# relay_m66.net
KiCad netlist of a schematic drawn in Altium Designer
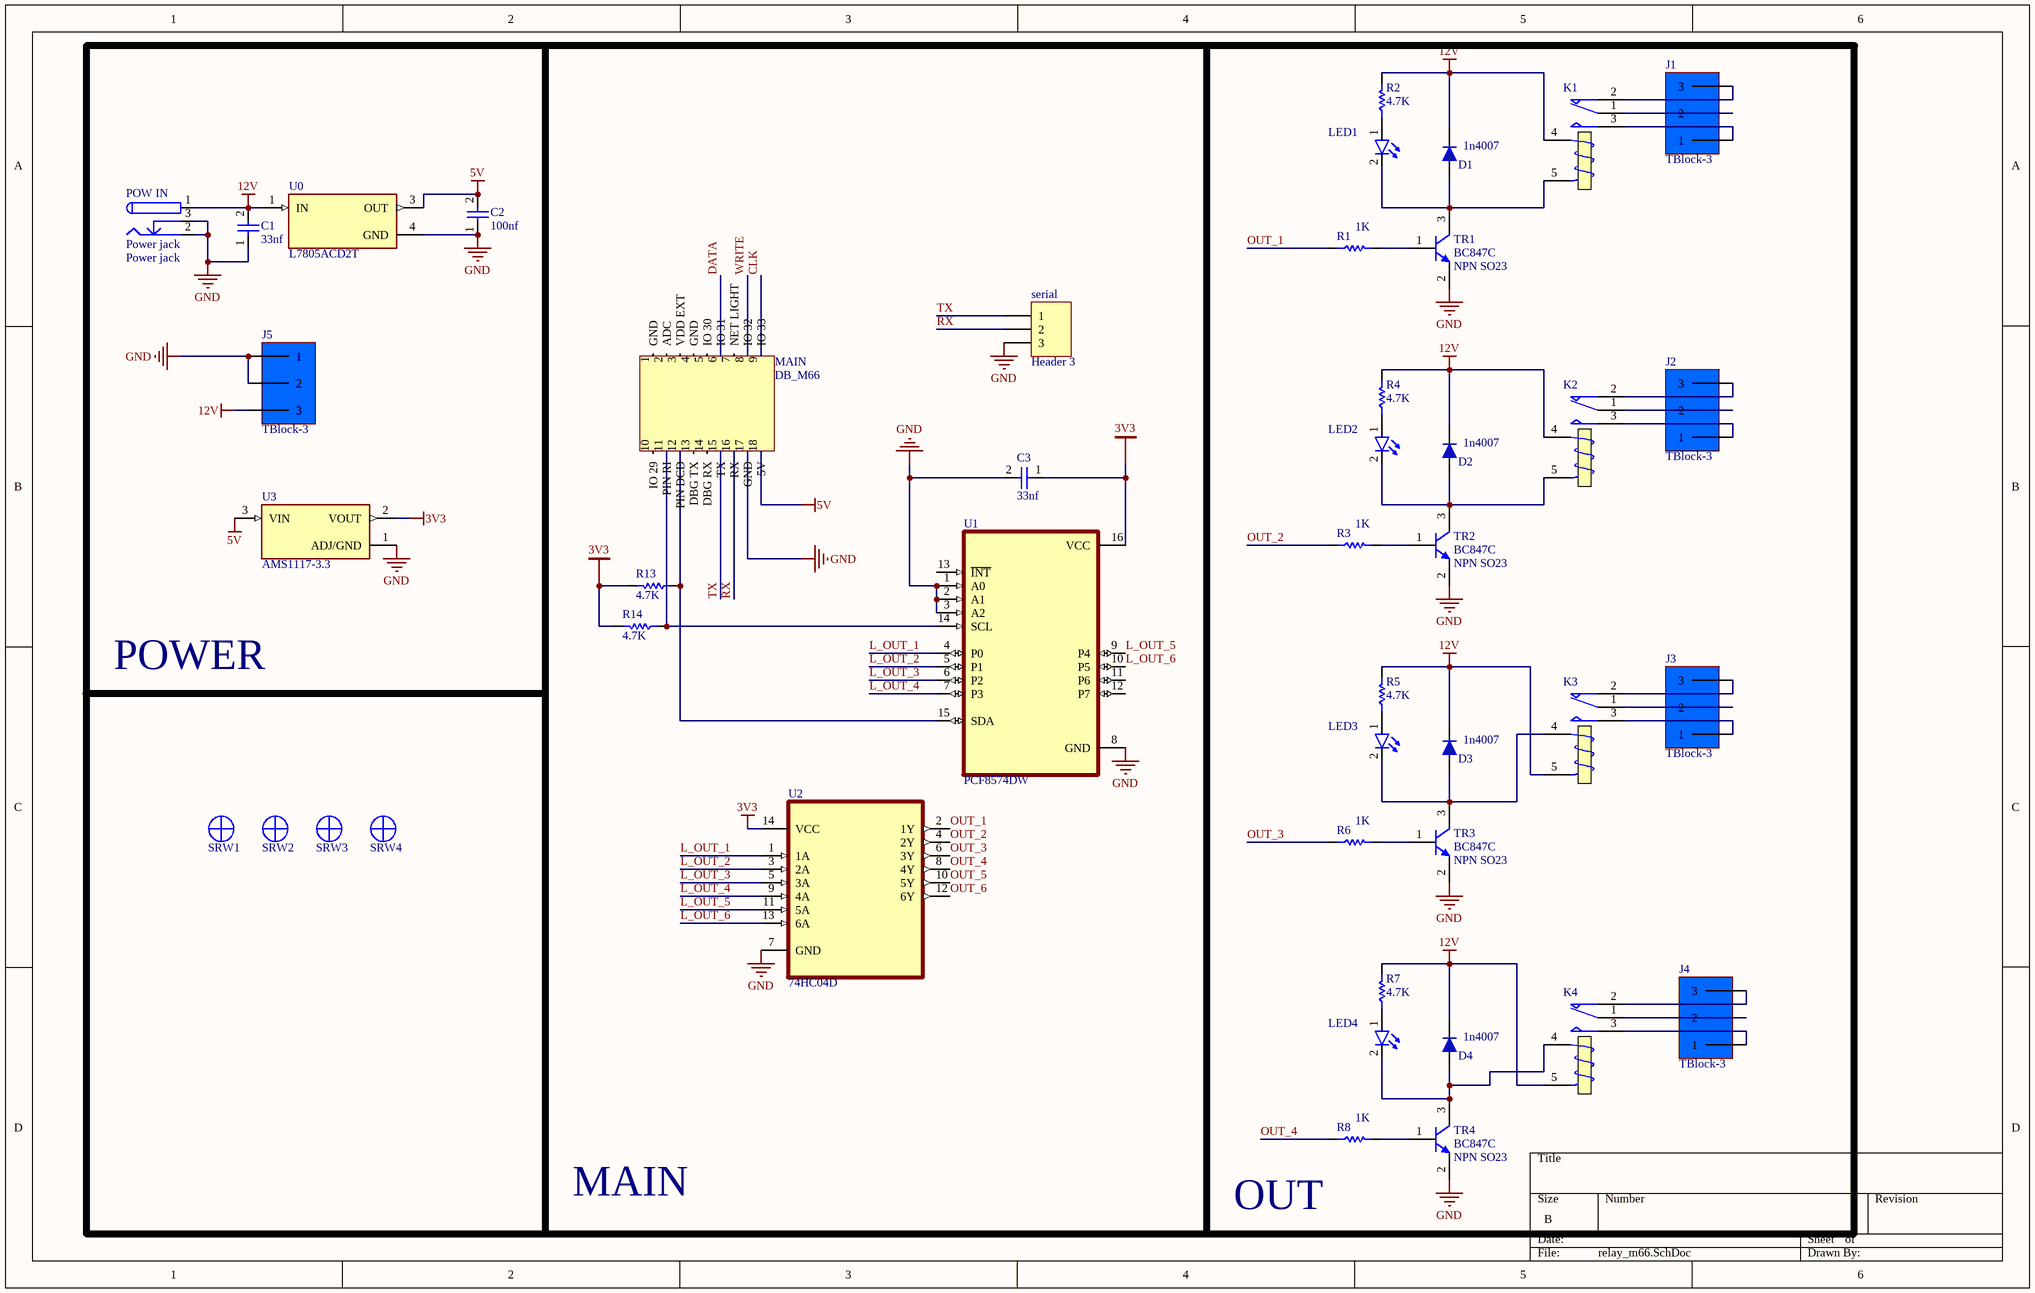
[diagram p0: relay_m66.SchDoc]

(export (version "E")
  (design (tool "Eeschema 10.0.6"))
  (components
    (comp (ref "C1") (value "33nf") (footprint "SMD 0805") (libsource (lib "3D LIB") (part "CAP NON")))
    (comp (ref "C2") (value "100nf") (footprint "SMD 0805") (libsource (lib "3D LIB") (part "CAP NON")))
    (comp (ref "C3") (value "33nf") (footprint "SMD 0805") (libsource (lib "3D LIB") (part "CAP NON")))
    (comp (ref "D1")
      (value "1n4007")
      (footprint "DIOM4629X24N")
      (description "Standard Rectifiers")
      (fields (field (name "MANUFACTURER") "DC COMPONENTS") (field (name "DESIGNER") "Abbas Basereh"))
      (libsource (lib "Altium") (part "1n4007 SMD M7"))
    )
    (comp (ref "D2")
      (value "1n4007")
      (footprint "DIOM4629X24N")
      (description "Standard Rectifiers")
      (fields (field (name "MANUFACTURER") "DC COMPONENTS") (field (name "DESIGNER") "Abbas Basereh"))
      (libsource (lib "Altium") (part "1n4007 SMD M7"))
    )
    (comp (ref "D3")
      (value "1n4007")
      (footprint "DIOM4629X24N")
      (description "Standard Rectifiers")
      (fields (field (name "MANUFACTURER") "DC COMPONENTS") (field (name "DESIGNER") "Abbas Basereh"))
      (libsource (lib "Altium") (part "1n4007 SMD M7"))
    )
    (comp (ref "D4")
      (value "1n4007")
      (footprint "DIOM4629X24N")
      (description "Standard Rectifiers")
      (fields (field (name "MANUFACTURER") "DC COMPONENTS") (field (name "DESIGNER") "Abbas Basereh"))
      (libsource (lib "Altium") (part "1n4007 SMD M7"))
    )
    (comp (ref "J1")
      (value "TBlock-3")
      (footprint "KF300-3 PIN")
      (libsource (lib "AltiumLib1") (part "TBlock-3"))
    )
    (comp (ref "J2")
      (value "TBlock-3")
      (footprint "KF300-3 PIN")
      (libsource (lib "AltiumLib1") (part "TBlock-3"))
    )
    (comp (ref "J3")
      (value "TBlock-3")
      (footprint "KF300-3 PIN")
      (libsource (lib "AltiumLib1") (part "TBlock-3"))
    )
    (comp (ref "J4")
      (value "TBlock-3")
      (footprint "KF300-3 PIN")
      (libsource (lib "AltiumLib1") (part "TBlock-3"))
    )
    (comp (ref "J5") (value "TBlock-3") (footprint "KF300-3 PIN") (libsource (lib "") (part "TBlock-3_1")))
    (comp (ref "K1")
      (value "~")
      (footprint "Relay 18.85x15.35x15.70")
      (description "Single-Pole Dual-Throw Relay")
      (fields (field (name "DESIGNER") "Abbas Basereh"))
      (libsource (lib "2017Basereh -ver1") (part "Relay_SPDT"))
    )
    (comp (ref "K2")
      (value "~")
      (footprint "Relay 18.85x15.35x15.70")
      (description "Single-Pole Dual-Throw Relay")
      (fields (field (name "DESIGNER") "Abbas Basereh"))
      (libsource (lib "2017Basereh -ver1") (part "Relay_SPDT"))
    )
    (comp (ref "K3")
      (value "~")
      (footprint "Relay 18.85x15.35x15.70")
      (description "Single-Pole Dual-Throw Relay")
      (fields (field (name "DESIGNER") "Abbas Basereh"))
      (libsource (lib "2017Basereh -ver1") (part "Relay_SPDT"))
    )
    (comp (ref "K4")
      (value "~")
      (footprint "Relay 18.85x15.35x15.70")
      (description "Single-Pole Dual-Throw Relay")
      (fields (field (name "DESIGNER") "Abbas Basereh"))
      (libsource (lib "2017Basereh -ver1") (part "Relay_SPDT"))
    )
    (comp (ref "LED1") (value "LED 2PIN") (footprint "LED 0805") (libsource (lib "3D LIB") (part "LED 2PIN")))
    (comp (ref "LED2") (value "LED 2PIN") (footprint "LED 0805") (libsource (lib "3D LIB") (part "LED 2PIN")))
    (comp (ref "LED3") (value "LED 2PIN") (footprint "LED 0805") (libsource (lib "3D LIB") (part "LED 2PIN")))
    (comp (ref "LED4") (value "LED 2PIN") (footprint "LED 0805") (libsource (lib "3D LIB") (part "LED 2PIN")))
    (comp (ref "MAIN") (value "DB_M66") (footprint "DB_M66") (libsource (lib "mahdi_h") (part "DB_M66")))
    (comp (ref "POW IN")
      (value "Power jack")
      (footprint "Power Jack")
      (fields (field (name "ALTIUM_UNNAMED_1") "Power jack"))
      (libsource (lib "3D LIB") (part "Power jack"))
    )
    (comp (ref "R1") (value "1K") (footprint "0805_1/8W") (libsource (lib "3D LIB") (part "RESISTOR")))
    (comp (ref "R2") (value "4.7K") (footprint "0805_1/8W") (libsource (lib "3D LIB") (part "RESISTOR")))
    (comp (ref "R3") (value "1K") (footprint "0805_1/8W") (libsource (lib "3D LIB") (part "RESISTOR")))
    (comp (ref "R4") (value "4.7K") (footprint "0805_1/8W") (libsource (lib "3D LIB") (part "RESISTOR")))
    (comp (ref "R5") (value "4.7K") (footprint "0805_1/8W") (libsource (lib "3D LIB") (part "RESISTOR")))
    (comp (ref "R6") (value "1K") (footprint "0805_1/8W") (libsource (lib "3D LIB") (part "RESISTOR")))
    (comp (ref "R7") (value "4.7K") (footprint "0805_1/8W") (libsource (lib "3D LIB") (part "RESISTOR")))
    (comp (ref "R8") (value "1K") (footprint "0805_1/8W") (libsource (lib "3D LIB") (part "RESISTOR")))
    (comp (ref "R13") (value "4.7K") (footprint "0805_1/8W") (libsource (lib "3D LIB") (part "RESISTOR")))
    (comp (ref "R14") (value "4.7K") (footprint "0805_1/8W") (libsource (lib "3D LIB") (part "RESISTOR")))
    (comp (ref "serial")
      (value "Header 3")
      (footprint "HDR1X3")
      (description "Header, 3-Pin")
      (fields (field (name "PUBLISHER") "Altium Limited"))
      (libsource (lib "Miscellaneous Connectors") (part "Header 3"))
    )
    (comp (ref "SRW1")
      (value "Screw")
      (footprint "Board Screw")
      (description "Board Screw With Spacer")
      (libsource (lib "Altium") (part "Board Screw 3MM"))
    )
    (comp (ref "SRW2")
      (value "Screw")
      (footprint "Board Screw")
      (description "Board Screw With Spacer")
      (libsource (lib "Altium") (part "Board Screw 3MM"))
    )
    (comp (ref "SRW3")
      (value "Screw")
      (footprint "Board Screw")
      (description "Board Screw With Spacer")
      (libsource (lib "Altium") (part "Board Screw 3MM"))
    )
    (comp (ref "SRW4")
      (value "Screw")
      (footprint "Board Screw")
      (description "Board Screw With Spacer")
      (libsource (lib "Altium") (part "Board Screw 3MM"))
    )
    (comp (ref "TR1")
      (value "BC847C")
      (footprint "SOT23_BEC_M")
      (fields (field (name "ALTIUM_UNNAMED_2") "NPN SO23"))
      (libsource (lib "3D LIB") (part "NPN SMD"))
    )
    (comp (ref "TR2")
      (value "BC847C")
      (footprint "SOT23_BEC_M")
      (fields (field (name "ALTIUM_UNNAMED_2") "NPN SO23"))
      (libsource (lib "3D LIB") (part "NPN SMD"))
    )
    (comp (ref "TR3")
      (value "BC847C")
      (footprint "SOT23_BEC_M")
      (fields (field (name "ALTIUM_UNNAMED_2") "NPN SO23"))
      (libsource (lib "3D LIB") (part "NPN SMD"))
    )
    (comp (ref "TR4")
      (value "BC847C")
      (footprint "SOT23_BEC_M")
      (fields (field (name "ALTIUM_UNNAMED_2") "NPN SO23"))
      (libsource (lib "3D LIB") (part "NPN SMD"))
    )
    (comp (ref "U0")
      (value "L7805ACD2T")
      (footprint "VREG_L7805ACD2T")
      (description "Linear Voltage Regulator IC 1 Output 1.5A D2PAK")
      (fields (field (name "MF") "STMicroelectronics"))
      (libsource (lib "L7805ACD2T") (part "L7805ACD2T"))
    )
    (comp (ref "U1")
      (value "PCF8574DW")
      (footprint "SOIC127P1030X265-16N")
      (description "Remote 8-Bit I/O Expander for I2C-Bus 16-SOIC -40 to 85")
      (fields (field (name "MF") "Texas Instruments"))
      (libsource (lib "PCF8574DW") (part "PCF8574DW"))
    )
    (comp (ref "U2")
      (value "74HC04D")
      (footprint "SOIC127P600X175-14N")
      (description "Inverter IC 6 Channel 14-SOIC")
      (fields (field (name "MF") "Toshiba"))
      (libsource (lib "74HC04D") (part "74HC04D"))
    )
    (comp (ref "U3")
      (value "AMS1117-3.3")
      (footprint "SOT229P700X180-4N")
      (description "Sot223/Pkg 1-Amp 3.3-Volt Low Drop Out Voltage Regulatator")
      (fields (field (name "MF") "Advanced Monolithic Systems"))
      (libsource (lib "AMS1117-3.3") (part "AMS1117-3.3"))
    )
  )
  (nets
    (net (code "1") (name "/CLK") (class "Default")
      (node (ref "MAIN") (pin "9") (pinfunction "IO_33_9") (pintype "passive"))
    )
    (net (code "2") (name "/DATA") (class "Default")
      (node (ref "MAIN") (pin "6") (pinfunction "IO_31_6") (pintype "passive"))
    )
    (net (code "3") (name "/L_OUT_1") (class "Default")
      (node (ref "U1") (pin "4") (pinfunction "P0_4") (pintype "bidirectional"))
      (node (ref "U2") (pin "1") (pinfunction "1A_1") (pintype "input"))
    )
    (net (code "4") (name "/L_OUT_2") (class "Default")
      (node (ref "U1") (pin "5") (pinfunction "P1_5") (pintype "bidirectional"))
      (node (ref "U2") (pin "3") (pinfunction "2A_3") (pintype "input"))
    )
    (net (code "5") (name "/L_OUT_3") (class "Default")
      (node (ref "U1") (pin "6") (pinfunction "P2_6") (pintype "bidirectional"))
      (node (ref "U2") (pin "5") (pinfunction "3A_5") (pintype "input"))
    )
    (net (code "6") (name "/L_OUT_4") (class "Default")
      (node (ref "U1") (pin "7") (pinfunction "P3_7") (pintype "bidirectional"))
      (node (ref "U2") (pin "9") (pinfunction "4A_9") (pintype "input"))
    )
    (net (code "7") (name "/L_OUT_5") (class "Default")
      (node (ref "U1") (pin "9") (pinfunction "P4_9") (pintype "bidirectional"))
      (node (ref "U2") (pin "11") (pinfunction "5A_11") (pintype "input"))
    )
    (net (code "8") (name "/L_OUT_6") (class "Default")
      (node (ref "U1") (pin "10") (pinfunction "P5_10") (pintype "bidirectional"))
      (node (ref "U2") (pin "13") (pinfunction "6A_13") (pintype "input"))
    )
    (net (code "9") (name "/OUT_1") (class "Default")
      (node (ref "R1") (pin "1") (pinfunction "1_1") (pintype "passive"))
      (node (ref "U2") (pin "2") (pinfunction "1Y_2") (pintype "output"))
    )
    (net (code "10") (name "/OUT_2") (class "Default")
      (node (ref "R3") (pin "1") (pinfunction "1_1") (pintype "passive"))
      (node (ref "U2") (pin "4") (pinfunction "2Y_4") (pintype "output"))
    )
    (net (code "11") (name "/OUT_3") (class "Default")
      (node (ref "R6") (pin "1") (pinfunction "1_1") (pintype "passive"))
      (node (ref "U2") (pin "6") (pinfunction "3Y_6") (pintype "output"))
    )
    (net (code "12") (name "/OUT_4") (class "Default")
      (node (ref "R8") (pin "1") (pinfunction "1_1") (pintype "passive"))
      (node (ref "U2") (pin "8") (pinfunction "4Y_8") (pintype "output"))
    )
    (net (code "13") (name "/OUT_5") (class "Default")
      (node (ref "U2") (pin "10") (pinfunction "5Y_10") (pintype "output"))
    )
    (net (code "14") (name "/OUT_6") (class "Default")
      (node (ref "U2") (pin "12") (pinfunction "6Y_12") (pintype "output"))
    )
    (net (code "15") (name "/RX") (class "Default")
      (node (ref "MAIN") (pin "16") (pinfunction "RX_16") (pintype "passive"))
      (node (ref "serial") (pin "2") (pinfunction "2_2") (pintype "passive"))
    )
    (net (code "16") (name "/TX") (class "Default")
      (node (ref "MAIN") (pin "15") (pinfunction "TX_15") (pintype "passive"))
      (node (ref "serial") (pin "1") (pinfunction "1_1") (pintype "passive"))
    )
    (net (code "17") (name "/WRITE") (class "Default")
      (node (ref "MAIN") (pin "8") (pinfunction "IO_32_8") (pintype "passive"))
    )
    (net (code "18") (name "3V3") (class "Default")
      (node (ref "C3") (pin "1") (pinfunction "1_1") (pintype "passive"))
      (node (ref "R13") (pin "2") (pinfunction "2_2") (pintype "passive"))
      (node (ref "R14") (pin "2") (pinfunction "2_2") (pintype "passive"))
      (node (ref "U1") (pin "16") (pinfunction "VCC_16") (pintype "power_in"))
      (node (ref "U2") (pin "14") (pinfunction "VCC_14") (pintype "power_in"))
      (node (ref "U3") (pin "2") (pinfunction "VOUT_2") (pintype "output"))
    )
    (net (code "19") (name "5V") (class "Default")
      (node (ref "C2") (pin "2") (pinfunction "2_2") (pintype "passive"))
      (node (ref "MAIN") (pin "18") (pinfunction "5V_18") (pintype "passive"))
      (node (ref "U0") (pin "3") (pinfunction "OUT_3") (pintype "output"))
      (node (ref "U3") (pin "3") (pinfunction "VIN_3") (pintype "input"))
    )
    (net (code "20") (name "12V") (class "Default")
      (node (ref "C1") (pin "2") (pinfunction "2_2") (pintype "passive"))
      (node (ref "D1") (pin "2") (pintype "passive"))
      (node (ref "D2") (pin "2") (pintype "passive"))
      (node (ref "D3") (pin "2") (pintype "passive"))
      (node (ref "D4") (pin "2") (pintype "passive"))
      (node (ref "J5") (pin "3") (pinfunction "3_3") (pintype "passive"))
      (node (ref "K1") (pin "4") (pinfunction "T1_4") (pintype "passive"))
      (node (ref "K2") (pin "4") (pinfunction "T1_4") (pintype "passive"))
      (node (ref "K3") (pin "5") (pinfunction "T2_5") (pintype "passive"))
      (node (ref "K4") (pin "5") (pinfunction "T2_5") (pintype "passive"))
      (node (ref "POW IN") (pin "1") (pinfunction "1_1") (pintype "power_in"))
      (node (ref "R2") (pin "2") (pinfunction "2_2") (pintype "passive"))
      (node (ref "R4") (pin "2") (pinfunction "2_2") (pintype "passive"))
      (node (ref "R5") (pin "2") (pinfunction "2_2") (pintype "passive"))
      (node (ref "R7") (pin "2") (pinfunction "2_2") (pintype "passive"))
      (node (ref "U0") (pin "1") (pinfunction "IN_1") (pintype "input"))
    )
    (net (code "21") (name "GND") (class "Default")
      (node (ref "C1") (pin "1") (pinfunction "1_1") (pintype "passive"))
      (node (ref "C2") (pin "1") (pinfunction "1_1") (pintype "passive"))
      (node (ref "C3") (pin "2") (pinfunction "2_2") (pintype "passive"))
      (node (ref "J5") (pin "1") (pinfunction "1_1") (pintype "passive"))
      (node (ref "J5") (pin "2") (pinfunction "2_2") (pintype "passive"))
      (node (ref "MAIN") (pin "17") (pinfunction "GND_17") (pintype "passive"))
      (node (ref "POW IN") (pin "2") (pinfunction "2_2") (pintype "power_in"))
      (node (ref "POW IN") (pin "3") (pinfunction "3_3") (pintype "power_in"))
      (node (ref "TR1") (pin "2") (pinfunction "E_2") (pintype "passive"))
      (node (ref "TR2") (pin "2") (pinfunction "E_2") (pintype "passive"))
      (node (ref "TR3") (pin "2") (pinfunction "E_2") (pintype "passive"))
      (node (ref "TR4") (pin "2") (pinfunction "E_2") (pintype "passive"))
      (node (ref "U0") (pin "4") (pinfunction "GND_4") (pintype "power_in"))
      (node (ref "U1") (pin "1") (pinfunction "A0_1") (pintype "input"))
      (node (ref "U1") (pin "2") (pinfunction "A1_2") (pintype "input"))
      (node (ref "U1") (pin "3") (pinfunction "A2_3") (pintype "input"))
      (node (ref "U1") (pin "8") (pinfunction "GND_8") (pintype "power_in"))
      (node (ref "U2") (pin "7") (pinfunction "GND_7") (pintype "passive"))
      (node (ref "U3") (pin "1") (pinfunction "ADJ/GND_1") (pintype "power_in"))
      (node (ref "serial") (pin "3") (pinfunction "3_3") (pintype "passive"))
    )
    (net (code "22") (name "Net-(K1-COM)") (class "Default")
      (node (ref "J1") (pin "2") (pinfunction "2_2") (pintype "passive"))
      (node (ref "K1") (pin "1") (pinfunction "COM_1") (pintype "passive"))
    )
    (net (code "23") (name "Net-(K1-NC)") (class "Default")
      (node (ref "J1") (pin "3") (pinfunction "3_3") (pintype "passive"))
      (node (ref "K1") (pin "2") (pinfunction "NC_2") (pintype "passive"))
    )
    (net (code "24") (name "Net-(K1-NO)") (class "Default")
      (node (ref "J1") (pin "1") (pinfunction "1_1") (pintype "passive"))
      (node (ref "K1") (pin "3") (pinfunction "NO_3") (pintype "passive"))
    )
    (net (code "25") (name "Net-(K1-T2)") (class "Default")
      (node (ref "D1") (pin "1") (pintype "passive"))
      (node (ref "K1") (pin "5") (pinfunction "T2_5") (pintype "passive"))
      (node (ref "LED1") (pin "2") (pinfunction "K_2") (pintype "passive"))
      (node (ref "TR1") (pin "3") (pinfunction "C_3") (pintype "passive"))
    )
    (net (code "26") (name "Net-(K2-COM)") (class "Default")
      (node (ref "J2") (pin "2") (pinfunction "2_2") (pintype "passive"))
      (node (ref "K2") (pin "1") (pinfunction "COM_1") (pintype "passive"))
    )
    (net (code "27") (name "Net-(K2-NC)") (class "Default")
      (node (ref "J2") (pin "3") (pinfunction "3_3") (pintype "passive"))
      (node (ref "K2") (pin "2") (pinfunction "NC_2") (pintype "passive"))
    )
    (net (code "28") (name "Net-(K2-NO)") (class "Default")
      (node (ref "J2") (pin "1") (pinfunction "1_1") (pintype "passive"))
      (node (ref "K2") (pin "3") (pinfunction "NO_3") (pintype "passive"))
    )
    (net (code "29") (name "Net-(K2-T2)") (class "Default")
      (node (ref "D2") (pin "1") (pintype "passive"))
      (node (ref "K2") (pin "5") (pinfunction "T2_5") (pintype "passive"))
      (node (ref "LED2") (pin "2") (pinfunction "K_2") (pintype "passive"))
      (node (ref "TR2") (pin "3") (pinfunction "C_3") (pintype "passive"))
    )
    (net (code "30") (name "Net-(K3-COM)") (class "Default")
      (node (ref "J3") (pin "2") (pinfunction "2_2") (pintype "passive"))
      (node (ref "K3") (pin "1") (pinfunction "COM_1") (pintype "passive"))
    )
    (net (code "31") (name "Net-(K3-NC)") (class "Default")
      (node (ref "J3") (pin "3") (pinfunction "3_3") (pintype "passive"))
      (node (ref "K3") (pin "2") (pinfunction "NC_2") (pintype "passive"))
    )
    (net (code "32") (name "Net-(K3-NO)") (class "Default")
      (node (ref "J3") (pin "1") (pinfunction "1_1") (pintype "passive"))
      (node (ref "K3") (pin "3") (pinfunction "NO_3") (pintype "passive"))
    )
    (net (code "33") (name "Net-(K3-T1)") (class "Default")
      (node (ref "D3") (pin "1") (pintype "passive"))
      (node (ref "K3") (pin "4") (pinfunction "T1_4") (pintype "passive"))
      (node (ref "LED3") (pin "2") (pinfunction "K_2") (pintype "passive"))
      (node (ref "TR3") (pin "3") (pinfunction "C_3") (pintype "passive"))
    )
    (net (code "34") (name "Net-(K4-COM)") (class "Default")
      (node (ref "J4") (pin "2") (pinfunction "2_2") (pintype "passive"))
      (node (ref "K4") (pin "1") (pinfunction "COM_1") (pintype "passive"))
    )
    (net (code "35") (name "Net-(K4-NC)") (class "Default")
      (node (ref "J4") (pin "3") (pinfunction "3_3") (pintype "passive"))
      (node (ref "K4") (pin "2") (pinfunction "NC_2") (pintype "passive"))
    )
    (net (code "36") (name "Net-(K4-NO)") (class "Default")
      (node (ref "J4") (pin "1") (pinfunction "1_1") (pintype "passive"))
      (node (ref "K4") (pin "3") (pinfunction "NO_3") (pintype "passive"))
    )
    (net (code "37") (name "Net-(K4-T1)") (class "Default")
      (node (ref "D4") (pin "1") (pintype "passive"))
      (node (ref "K4") (pin "4") (pinfunction "T1_4") (pintype "passive"))
      (node (ref "LED4") (pin "2") (pinfunction "K_2") (pintype "passive"))
      (node (ref "TR4") (pin "3") (pinfunction "C_3") (pintype "passive"))
    )
    (net (code "38") (name "Net-(LED1-A)") (class "Default")
      (node (ref "LED1") (pin "1") (pinfunction "A_1") (pintype "passive"))
      (node (ref "R2") (pin "1") (pinfunction "1_1") (pintype "passive"))
    )
    (net (code "39") (name "Net-(LED2-A)") (class "Default")
      (node (ref "LED2") (pin "1") (pinfunction "A_1") (pintype "passive"))
      (node (ref "R4") (pin "1") (pinfunction "1_1") (pintype "passive"))
    )
    (net (code "40") (name "Net-(LED3-A)") (class "Default")
      (node (ref "LED3") (pin "1") (pinfunction "A_1") (pintype "passive"))
      (node (ref "R5") (pin "1") (pinfunction "1_1") (pintype "passive"))
    )
    (net (code "41") (name "Net-(LED4-A)") (class "Default")
      (node (ref "LED4") (pin "1") (pinfunction "A_1") (pintype "passive"))
      (node (ref "R7") (pin "1") (pinfunction "1_1") (pintype "passive"))
    )
    (net (code "42") (name "Net-(MAIN-PIN_DCD)") (class "Default")
      (node (ref "MAIN") (pin "12") (pinfunction "PIN_DCD_12") (pintype "passive"))
      (node (ref "R13") (pin "1") (pinfunction "1_1") (pintype "passive"))
      (node (ref "U1") (pin "15") (pinfunction "SDA_15") (pintype "bidirectional"))
    )
    (net (code "43") (name "Net-(MAIN-PIN_RI)") (class "Default")
      (node (ref "MAIN") (pin "11") (pinfunction "PIN_RI_11") (pintype "passive"))
      (node (ref "R14") (pin "1") (pinfunction "1_1") (pintype "passive"))
      (node (ref "U1") (pin "14") (pinfunction "SCL_14") (pintype "input"))
    )
    (net (code "44") (name "Net-(TR1-B)") (class "Default")
      (node (ref "R1") (pin "2") (pinfunction "2_2") (pintype "passive"))
      (node (ref "TR1") (pin "1") (pinfunction "B_1") (pintype "passive"))
    )
    (net (code "45") (name "Net-(TR2-B)") (class "Default")
      (node (ref "R3") (pin "2") (pinfunction "2_2") (pintype "passive"))
      (node (ref "TR2") (pin "1") (pinfunction "B_1") (pintype "passive"))
    )
    (net (code "46") (name "Net-(TR3-B)") (class "Default")
      (node (ref "R6") (pin "2") (pinfunction "2_2") (pintype "passive"))
      (node (ref "TR3") (pin "1") (pinfunction "B_1") (pintype "passive"))
    )
    (net (code "47") (name "Net-(TR4-B)") (class "Default")
      (node (ref "R8") (pin "2") (pinfunction "2_2") (pintype "passive"))
      (node (ref "TR4") (pin "1") (pinfunction "B_1") (pintype "passive"))
    )
    (net (code "48") (name "unconnected-(MAIN-ADC-Pad2)") (class "Default")
      (node (ref "MAIN") (pin "2") (pinfunction "ADC_2") (pintype "passive"))
    )
    (net (code "49") (name "unconnected-(MAIN-DBG_RX-Pad14)") (class "Default")
      (node (ref "MAIN") (pin "14") (pinfunction "DBG_RX_14") (pintype "passive"))
    )
    (net (code "50") (name "unconnected-(MAIN-DBG_TX-Pad13)") (class "Default")
      (node (ref "MAIN") (pin "13") (pinfunction "DBG_TX_13") (pintype "passive"))
    )
    (net (code "51") (name "unconnected-(MAIN-GND-Pad1)") (class "Default")
      (node (ref "MAIN") (pin "1") (pinfunction "GND_1") (pintype "passive"))
    )
    (net (code "52") (name "unconnected-(MAIN-GND-Pad4)") (class "Default")
      (node (ref "MAIN") (pin "4") (pinfunction "GND_4") (pintype "passive"))
    )
    (net (code "53") (name "unconnected-(MAIN-IO_29-Pad10)") (class "Default")
      (node (ref "MAIN") (pin "10") (pinfunction "IO_29_10") (pintype "passive"))
    )
    (net (code "54") (name "unconnected-(MAIN-IO_30-Pad5)") (class "Default")
      (node (ref "MAIN") (pin "5") (pinfunction "IO_30_5") (pintype "passive"))
    )
    (net (code "55") (name "unconnected-(MAIN-NET_LIGHT-Pad7)") (class "Default")
      (node (ref "MAIN") (pin "7") (pinfunction "NET_LIGHT_7") (pintype "passive"))
    )
    (net (code "56") (name "unconnected-(MAIN-VDD_EXT-Pad3)") (class "Default")
      (node (ref "MAIN") (pin "3") (pinfunction "VDD_EXT_3") (pintype "passive"))
    )
    (net (code "57") (name "unconnected-(U1-P6-Pad11)") (class "Default")
      (node (ref "U1") (pin "11") (pinfunction "P6_11") (pintype "bidirectional"))
    )
    (net (code "58") (name "unconnected-(U1-P7-Pad12)") (class "Default")
      (node (ref "U1") (pin "12") (pinfunction "P7_12") (pintype "bidirectional"))
    )
    (net (code "59") (name "unconnected-(U1-~{INT}-Pad13)") (class "Default")
      (node (ref "U1") (pin "13") (pinfunction "~{INT}_13") (pintype "input"))
    )
  )
)
